# DC-DC_regulator.net
KiCad netlist of a schematic drawn in Altium Designer
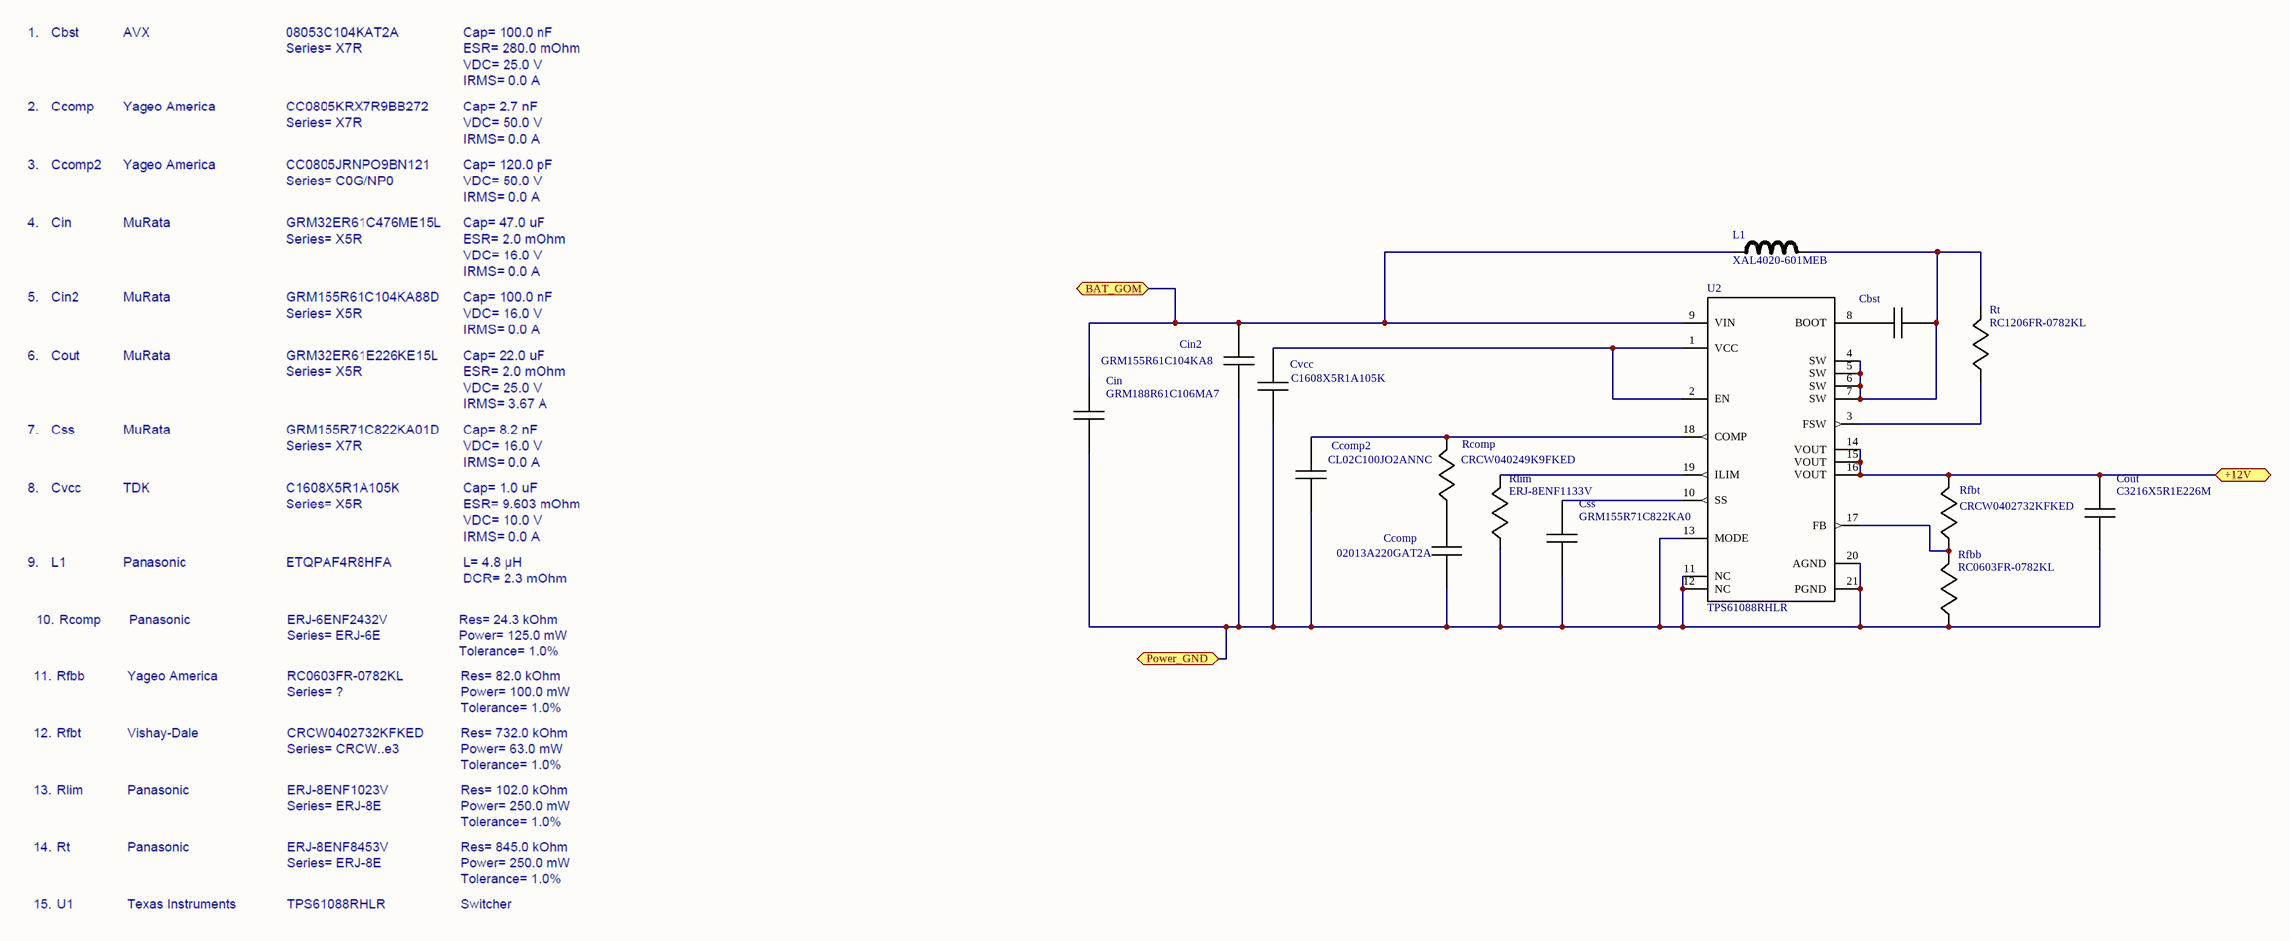
[diagram p0: DC-DC regulator.SchDoc]

(export (version "E")
  (design (tool "Eeschema 10.0.6"))
  (components
    (comp (ref "Cbst")
      (value "C1005X5R1A104K")
      (footprint "1005")
      (description "Imported")
      (libsource (lib "2015-10-09_12-54-35") (part "C1005X5R1A104K"))
    )
    (comp (ref "Ccomp")
      (value "02013A220GAT2A")
      (footprint "0201")
      (description "Imported")
      (libsource (lib "2015-10-09_12-54-35") (part "02013A220GAT2A"))
    )
    (comp (ref "Ccomp2")
      (value "CL02C100JO2ANNC")
      (footprint "01005")
      (description "Imported")
      (libsource (lib "2015-10-09_12-54-35") (part "CL02C100JO2ANNC"))
    )
    (comp (ref "Cin")
      (value "GRM188R61C106MA7")
      (footprint "0603")
      (description "Imported")
      (fields (field (name "MANUFACTURER_PART_NUMBER") "GRM188R61C106MA73D"))
      (libsource (lib "2015-10-09_12-54-35") (part "GRM188R61C106MA7"))
    )
    (comp (ref "Cin2")
      (value "GRM155R61C104KA8")
      (footprint "0402")
      (description "Imported")
      (fields (field (name "MANUFACTURER_PART_NUMBER") "GRM155R61C104KA88D"))
      (libsource (lib "2015-10-09_12-54-35") (part "GRM155R61C104KA8"))
    )
    (comp (ref "Cout")
      (value "C3216X5R1E226M")
      (footprint "1206")
      (description "Imported")
      (libsource (lib "2015-10-09_12-54-35") (part "C3216X5R1E226M"))
    )
    (comp (ref "Css")
      (value "GRM155R71C822KA0")
      (footprint "0402")
      (description "Imported")
      (fields (field (name "MANUFACTURER_PART_NUMBER") "GRM155R71C822KA01D"))
      (libsource (lib "2015-10-09_12-54-35") (part "GRM155R71C822KA0"))
    )
    (comp (ref "Cvcc")
      (value "C1608X5R1A105K")
      (footprint "1608")
      (description "Imported")
      (libsource (lib "2015-10-09_12-54-35") (part "C1608X5R1A105K"))
    )
    (comp (ref "L1")
      (value "XAL4020-601MEB")
      (footprint "XAL4020")
      (description "Imported")
      (libsource (lib "2015-10-09_12-54-35") (part "XAL4020-601MEB"))
    )
    (comp (ref "Rcomp")
      (value "CRCW040249K9FKED")
      (footprint "0402")
      (description "Imported")
      (libsource (lib "2015-10-09_12-54-35") (part "CRCW040249K9FKED"))
    )
    (comp (ref "Rfbb")
      (value "RC0603FR-0782KL")
      (footprint "0603")
      (description "Imported")
      (libsource (lib "2015-10-09_12-54-35") (part "RC0603FR-0782KL"))
    )
    (comp (ref "Rfbt")
      (value "CRCW0402732KFKED")
      (footprint "0402")
      (description "Imported")
      (libsource (lib "2015-10-09_12-54-35") (part "CRCW0402732KFKED"))
    )
    (comp (ref "Rlim")
      (value "ERJ-8ENF1133V")
      (footprint "1206")
      (description "Imported")
      (libsource (lib "2015-10-09_12-54-35") (part "ERJ-8ENF1133V"))
    )
    (comp (ref "Rt")
      (value "RC1206FR-0782KL")
      (footprint "1206")
      (description "Imported")
      (libsource (lib "2015-10-09_12-54-35") (part "RC1206FR-0782KL"))
    )
    (comp (ref "U2")
      (value "TPS61088RHLR")
      (footprint "RHL0020A")
      (description "Imported")
      (fields
        (field (name "ALTERNATE PARTNUMBER") "TPS61088RHLT")
        (field (name "MANUFACTURER") "Texas Instruments")
      )
      (libsource (lib "2015-10-09_12-53-27") (part "TPS61088RHLR"))
    )
  )
  (nets
    (net (code "1") (name "/+12V") (class "Default")
      (node (ref "Cout") (pin "1") (pinfunction "1_1") (pintype "passive"))
      (node (ref "Rfbt") (pin "1") (pinfunction "1_1") (pintype "passive"))
      (node (ref "U2") (pin "14") (pinfunction "VOUT_14") (pintype "passive"))
      (node (ref "U2") (pin "15") (pinfunction "VOUT_15") (pintype "passive"))
      (node (ref "U2") (pin "16") (pinfunction "VOUT_16") (pintype "passive"))
    )
    (net (code "2") (name "/BAT_GOM") (class "Default")
      (node (ref "Cin") (pin "1") (pinfunction "1_1") (pintype "passive"))
      (node (ref "Cin2") (pin "1") (pinfunction "1_1") (pintype "passive"))
      (node (ref "L1") (pin "1") (pinfunction "1_1") (pintype "passive"))
      (node (ref "U2") (pin "9") (pinfunction "VIN_9") (pintype "passive"))
    )
    (net (code "3") (name "/Power_GND") (class "Default")
      (node (ref "Ccomp") (pin "2") (pinfunction "2_2") (pintype "passive"))
      (node (ref "Ccomp2") (pin "1") (pinfunction "1_1") (pintype "passive"))
      (node (ref "Cin") (pin "2") (pinfunction "2_2") (pintype "passive"))
      (node (ref "Cin2") (pin "2") (pinfunction "2_2") (pintype "passive"))
      (node (ref "Cout") (pin "2") (pinfunction "2_2") (pintype "passive"))
      (node (ref "Css") (pin "1") (pinfunction "1_1") (pintype "passive"))
      (node (ref "Cvcc") (pin "1") (pinfunction "1_1") (pintype "passive"))
      (node (ref "Rfbb") (pin "2") (pinfunction "2_2") (pintype "passive"))
      (node (ref "Rlim") (pin "2") (pinfunction "2_2") (pintype "passive"))
      (node (ref "U2") (pin "11") (pinfunction "NC_11") (pintype "passive"))
      (node (ref "U2") (pin "12") (pinfunction "NC_12") (pintype "passive"))
      (node (ref "U2") (pin "13") (pinfunction "MODE_13") (pintype "passive"))
      (node (ref "U2") (pin "20") (pinfunction "AGND_20") (pintype "passive"))
      (node (ref "U2") (pin "21") (pinfunction "PGND_21") (pintype "passive"))
    )
    (net (code "4") (name "Net-(Cbst-Pad1)") (class "Default")
      (node (ref "Cbst") (pin "1") (pinfunction "1_1") (pintype "passive"))
      (node (ref "L1") (pin "2") (pinfunction "2_2") (pintype "passive"))
      (node (ref "Rt") (pin "1") (pinfunction "1_1") (pintype "passive"))
      (node (ref "U2") (pin "4") (pinfunction "SW_4") (pintype "power_in"))
      (node (ref "U2") (pin "5") (pinfunction "SW_5") (pintype "power_in"))
      (node (ref "U2") (pin "6") (pinfunction "SW_6") (pintype "power_in"))
      (node (ref "U2") (pin "7") (pinfunction "SW_7") (pintype "power_in"))
    )
    (net (code "5") (name "Net-(Ccomp-Pad1)") (class "Default")
      (node (ref "Ccomp") (pin "1") (pinfunction "1_1") (pintype "passive"))
      (node (ref "Rcomp") (pin "2") (pinfunction "2_2") (pintype "passive"))
    )
    (net (code "6") (name "Net-(U2-BOOT)") (class "Default")
      (node (ref "Cbst") (pin "2") (pinfunction "2_2") (pintype "passive"))
      (node (ref "U2") (pin "8") (pinfunction "BOOT_8") (pintype "power_in"))
    )
    (net (code "7") (name "Net-(U2-COMP)") (class "Default")
      (node (ref "Ccomp2") (pin "2") (pinfunction "2_2") (pintype "passive"))
      (node (ref "Rcomp") (pin "1") (pinfunction "1_1") (pintype "passive"))
      (node (ref "U2") (pin "18") (pinfunction "COMP_18") (pintype "output"))
    )
    (net (code "8") (name "Net-(U2-EN)") (class "Default")
      (node (ref "Cvcc") (pin "2") (pinfunction "2_2") (pintype "passive"))
      (node (ref "U2") (pin "1") (pinfunction "VCC_1") (pintype "passive"))
      (node (ref "U2") (pin "2") (pinfunction "EN_2") (pintype "passive"))
    )
    (net (code "9") (name "Net-(U2-FB)") (class "Default")
      (node (ref "Rfbb") (pin "1") (pinfunction "1_1") (pintype "passive"))
      (node (ref "Rfbt") (pin "2") (pinfunction "2_2") (pintype "passive"))
      (node (ref "U2") (pin "17") (pinfunction "FB_17") (pintype "output"))
    )
    (net (code "10") (name "Net-(U2-FSW)") (class "Default")
      (node (ref "Rt") (pin "2") (pinfunction "2_2") (pintype "passive"))
      (node (ref "U2") (pin "3") (pinfunction "FSW_3") (pintype "output"))
    )
    (net (code "11") (name "Net-(U2-ILIM)") (class "Default")
      (node (ref "Rlim") (pin "1") (pinfunction "1_1") (pintype "passive"))
      (node (ref "U2") (pin "19") (pinfunction "ILIM_19") (pintype "output"))
    )
    (net (code "12") (name "Net-(U2-SS)") (class "Default")
      (node (ref "Css") (pin "2") (pinfunction "2_2") (pintype "passive"))
      (node (ref "U2") (pin "10") (pinfunction "SS_10") (pintype "output"))
    )
  )
)
